# DualMonoPSU2.net
KiCad netlist of a schematic drawn in EAGLE
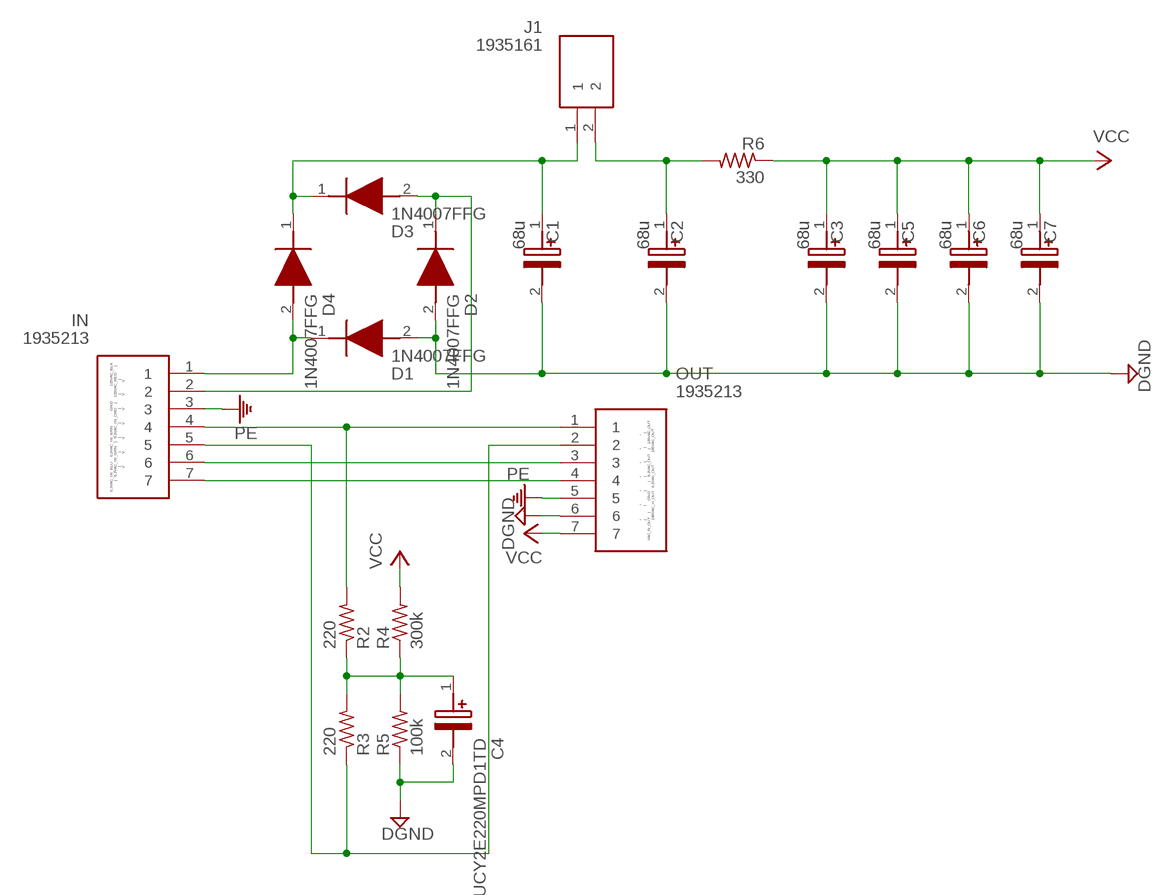
[diagram p0: schematic, sheet 1]

(export (version "E")
  (design (tool "Eeschema 10.0.6"))
  (components
    (comp (ref "C1")
      (value "68u")
      (footprint "eagle-import:CAPPRD750W80D1475H4700")
      (fields (field (name "MANUFACTURER_PART_NUMBER") "500HXW68MEFR14.5X45"))
      (libsource (lib "eagle-import") (part "500HXW68MEFR14.5X45"))
    )
    (comp (ref "C2")
      (value "68u")
      (footprint "eagle-import:CAPPRD750W80D1475H4700")
      (fields (field (name "MANUFACTURER_PART_NUMBER") "500HXW68MEFR14.5X45"))
      (libsource (lib "eagle-import") (part "500HXW68MEFR14.5X45"))
    )
    (comp (ref "C3")
      (value "68u")
      (footprint "eagle-import:CAPPRD750W80D1475H4700")
      (fields (field (name "MANUFACTURER_PART_NUMBER") "500HXW68MEFR14.5X45"))
      (libsource (lib "eagle-import") (part "500HXW68MEFR14.5X45"))
    )
    (comp (ref "C4")
      (value "UCY2E220MPD1TD")
      (footprint "eagle-import:CAPPRD500W60D1025H1750")
      (fields (field (name "MOUSER_PART_NUMBER") "647-UCY2E220MPD1TD"))
      (libsource (lib "eagle-import") (part "UCY2E220MPD1TD"))
    )
    (comp (ref "C5")
      (value "68u")
      (footprint "eagle-import:CAPPRD750W80D1475H4700")
      (fields (field (name "MANUFACTURER_PART_NUMBER") "500HXW68MEFR14.5X45"))
      (libsource (lib "eagle-import") (part "500HXW68MEFR14.5X45"))
    )
    (comp (ref "C6")
      (value "68u")
      (footprint "eagle-import:CAPPRD750W80D1475H4700")
      (fields (field (name "MANUFACTURER_PART_NUMBER") "500HXW68MEFR14.5X45"))
      (libsource (lib "eagle-import") (part "500HXW68MEFR14.5X45"))
    )
    (comp (ref "C7")
      (value "68u")
      (footprint "eagle-import:CAPPRD750W80D1475H4700")
      (fields (field (name "MANUFACTURER_PART_NUMBER") "500HXW68MEFR14.5X45"))
      (libsource (lib "eagle-import") (part "500HXW68MEFR14.5X45"))
    )
    (comp (ref "D1")
      (value "1N4007FFG")
      (footprint "eagle-import:DIOAD1405W86L465D235")
      (fields (field (name "MOUSER_PART_NUMBER") "863-1N4007FFG"))
      (libsource (lib "eagle-import") (part "1N4007FFG"))
    )
    (comp (ref "D2")
      (value "1N4007FFG")
      (footprint "eagle-import:DIOAD1405W86L465D235")
      (fields (field (name "MOUSER_PART_NUMBER") "863-1N4007FFG"))
      (libsource (lib "eagle-import") (part "1N4007FFG"))
    )
    (comp (ref "D3")
      (value "1N4007FFG")
      (footprint "eagle-import:DIOAD1405W86L465D235")
      (fields (field (name "MOUSER_PART_NUMBER") "863-1N4007FFG"))
      (libsource (lib "eagle-import") (part "1N4007FFG"))
    )
    (comp (ref "D4")
      (value "1N4007FFG")
      (footprint "eagle-import:DIOAD1405W86L465D235")
      (fields (field (name "MOUSER_PART_NUMBER") "863-1N4007FFG"))
      (libsource (lib "eagle-import") (part "1N4007FFG"))
    )
    (comp (ref "IN")
      (value "1935213")
      (footprint "eagle-import:1935213")
      (fields (field (name "MOUSER_PART_NUMBER") "651-1935213"))
      (libsource (lib "eagle-import") (part "1935213"))
    )
    (comp (ref "J1")
      (value "1935161")
      (footprint "eagle-import:1935161")
      (fields (field (name "MOUSER_PART_NUMBER") "651-1935161"))
      (libsource (lib "eagle-import") (part "1935161"))
    )
    (comp (ref "OUT")
      (value "1935213")
      (footprint "eagle-import:1935213")
      (fields (field (name "MOUSER_PART_NUMBER") "651-1935213"))
      (libsource (lib "eagle-import") (part "1935213"))
    )
    (comp (ref "R2")
      (value "220")
      (footprint "eagle-import:0411_15")
      (libsource (lib "eagle-import") (part "R-US_0411/15"))
    )
    (comp (ref "R3")
      (value "220")
      (footprint "eagle-import:0411_15")
      (libsource (lib "eagle-import") (part "R-US_0411/15"))
    )
    (comp (ref "R4")
      (value "300k")
      (footprint "eagle-import:0411_15")
      (libsource (lib "eagle-import") (part "R-US_0411/15"))
    )
    (comp (ref "R5")
      (value "100k")
      (footprint "eagle-import:0411_15")
      (libsource (lib "eagle-import") (part "R-US_0411/15"))
    )
    (comp (ref "R6")
      (value "330")
      (footprint "eagle-import:0411_15")
      (libsource (lib "eagle-import") (part "R-US_0411/15"))
    )
  )
  (nets
    (net (code "1") (name "DGND") (class "Default")
      (node (ref "C1") (pin "2") (pinfunction "-_2") (pintype "bidirectional"))
      (node (ref "C2") (pin "2") (pinfunction "-_2") (pintype "bidirectional"))
      (node (ref "C3") (pin "2") (pinfunction "-_2") (pintype "bidirectional"))
      (node (ref "C4") (pin "2") (pinfunction "-_2") (pintype "bidirectional"))
      (node (ref "C5") (pin "2") (pinfunction "-_2") (pintype "bidirectional"))
      (node (ref "C6") (pin "2") (pinfunction "-_2") (pintype "bidirectional"))
      (node (ref "C7") (pin "2") (pinfunction "-_2") (pintype "bidirectional"))
      (node (ref "D1") (pin "2") (pinfunction "A_2") (pintype "bidirectional"))
      (node (ref "D2") (pin "2") (pinfunction "A_2") (pintype "bidirectional"))
      (node (ref "OUT") (pin "6") (pinfunction "6_6") (pintype "bidirectional"))
      (node (ref "R5") (pin "1") (pinfunction "1_1") (pintype "passive"))
    )
    (net (code "2") (name "Net-(C1-+)") (class "Default")
      (node (ref "C1") (pin "1") (pinfunction "+_1") (pintype "bidirectional"))
      (node (ref "D3") (pin "1") (pinfunction "K_1") (pintype "bidirectional"))
      (node (ref "D4") (pin "1") (pinfunction "K_1") (pintype "bidirectional"))
      (node (ref "J1") (pin "1") (pinfunction "1_1") (pintype "bidirectional"))
    )
    (net (code "3") (name "Net-(C2-+)") (class "Default")
      (node (ref "C2") (pin "1") (pinfunction "+_1") (pintype "bidirectional"))
      (node (ref "J1") (pin "2") (pinfunction "2_2") (pintype "bidirectional"))
      (node (ref "R6") (pin "2") (pinfunction "2_2") (pintype "passive"))
    )
    (net (code "4") (name "Net-(C4-+)") (class "Default")
      (node (ref "C4") (pin "1") (pinfunction "+_1") (pintype "bidirectional"))
      (node (ref "R2") (pin "1") (pinfunction "1_1") (pintype "passive"))
      (node (ref "R3") (pin "2") (pinfunction "2_2") (pintype "passive"))
      (node (ref "R4") (pin "1") (pinfunction "1_1") (pintype "passive"))
      (node (ref "R5") (pin "2") (pinfunction "2_2") (pintype "passive"))
    )
    (net (code "5") (name "Net-(D1-K)") (class "Default")
      (node (ref "D1") (pin "1") (pinfunction "K_1") (pintype "bidirectional"))
      (node (ref "D4") (pin "2") (pinfunction "A_2") (pintype "bidirectional"))
      (node (ref "IN") (pin "1") (pinfunction "1_1") (pintype "bidirectional"))
    )
    (net (code "6") (name "Net-(D2-K)") (class "Default")
      (node (ref "D2") (pin "1") (pinfunction "K_1") (pintype "bidirectional"))
      (node (ref "D3") (pin "2") (pinfunction "A_2") (pintype "bidirectional"))
      (node (ref "IN") (pin "2") (pinfunction "2_2") (pintype "bidirectional"))
    )
    (net (code "7") (name "Net-(IN-Pad4)") (class "Default")
      (node (ref "IN") (pin "4") (pinfunction "4_4") (pintype "bidirectional"))
      (node (ref "OUT") (pin "1") (pinfunction "1_1") (pintype "bidirectional"))
      (node (ref "R2") (pin "2") (pinfunction "2_2") (pintype "passive"))
    )
    (net (code "8") (name "Net-(IN-Pad5)") (class "Default")
      (node (ref "IN") (pin "5") (pinfunction "5_5") (pintype "bidirectional"))
      (node (ref "OUT") (pin "2") (pinfunction "2_2") (pintype "bidirectional"))
      (node (ref "R3") (pin "1") (pinfunction "1_1") (pintype "passive"))
    )
    (net (code "9") (name "Net-(IN-Pad6)") (class "Default")
      (node (ref "IN") (pin "6") (pinfunction "6_6") (pintype "bidirectional"))
      (node (ref "OUT") (pin "3") (pinfunction "3_3") (pintype "bidirectional"))
    )
    (net (code "10") (name "Net-(IN-Pad7)") (class "Default")
      (node (ref "IN") (pin "7") (pinfunction "7_7") (pintype "bidirectional"))
      (node (ref "OUT") (pin "4") (pinfunction "4_4") (pintype "bidirectional"))
    )
    (net (code "11") (name "PE") (class "Default")
      (node (ref "IN") (pin "3") (pinfunction "3_3") (pintype "bidirectional"))
      (node (ref "OUT") (pin "5") (pinfunction "5_5") (pintype "bidirectional"))
    )
    (net (code "12") (name "VCC") (class "Default")
      (node (ref "C3") (pin "1") (pinfunction "+_1") (pintype "bidirectional"))
      (node (ref "C5") (pin "1") (pinfunction "+_1") (pintype "bidirectional"))
      (node (ref "C6") (pin "1") (pinfunction "+_1") (pintype "bidirectional"))
      (node (ref "C7") (pin "1") (pinfunction "+_1") (pintype "bidirectional"))
      (node (ref "OUT") (pin "7") (pinfunction "7_7") (pintype "bidirectional"))
      (node (ref "R4") (pin "2") (pinfunction "2_2") (pintype "passive"))
      (node (ref "R6") (pin "1") (pinfunction "1_1") (pintype "passive"))
    )
  )
)
